# AUDIO.net
KiCad netlist of a schematic drawn in Altium Designer
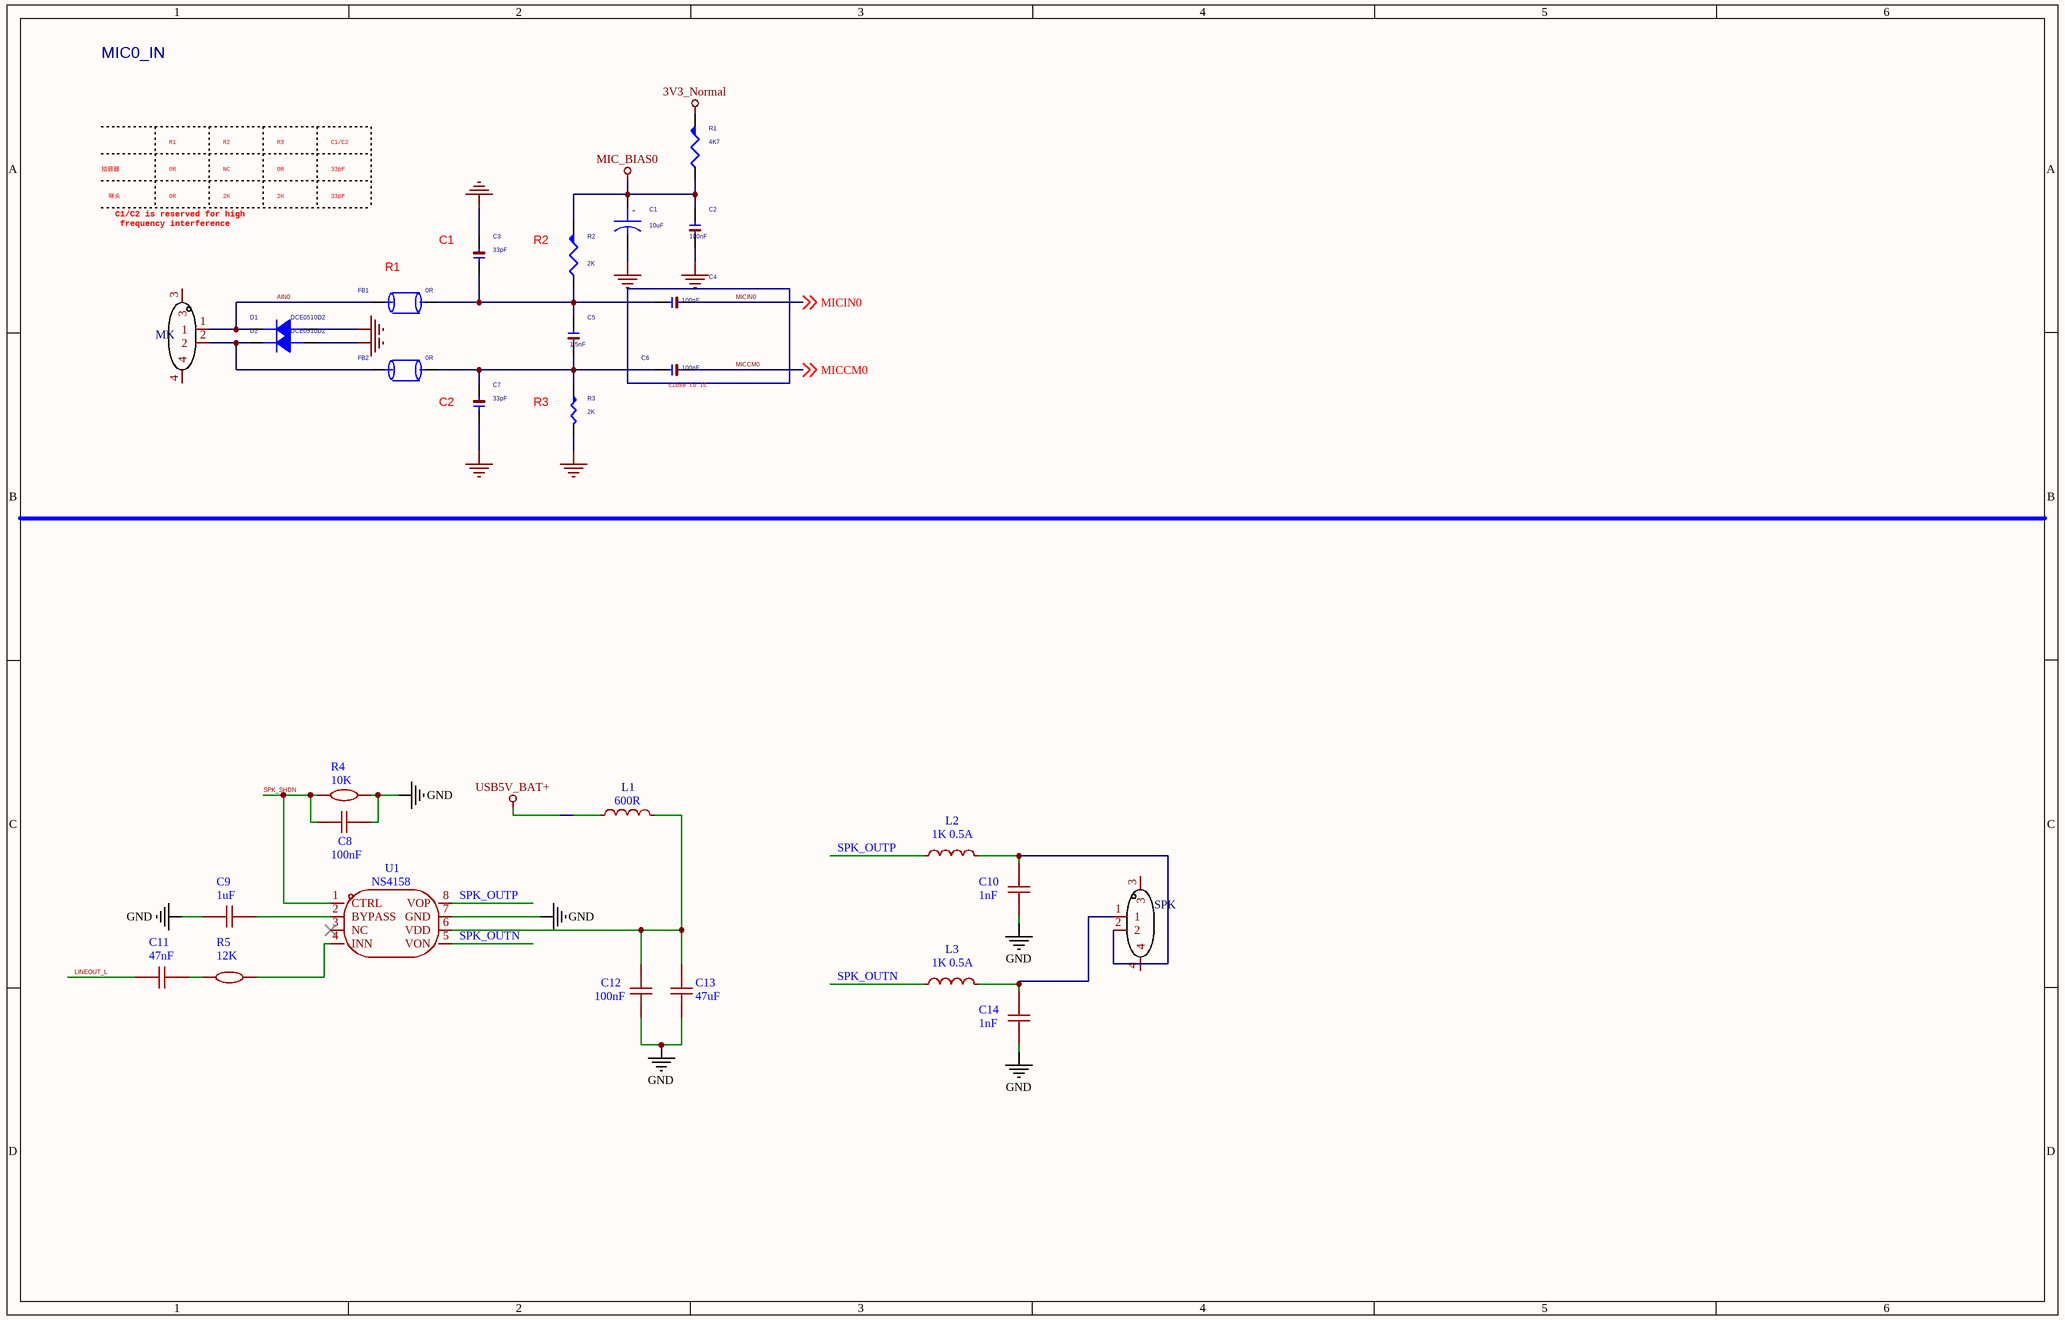
[diagram p0: AUDIO.SchDoc]

(export (version "E")
  (design (tool "Eeschema 10.0.6"))
  (components
    (comp (ref "C1") (value "10uF") (footprint "C0603") (libsource (lib "*") (part "CAP POL")))
    (comp (ref "C2") (value "100nF") (footprint "C0402") (libsource (lib "") (part "C0805_10uF_1")))
    (comp (ref "C3") (value "33pF") (footprint "C0402") (libsource (lib "*") (part "C0402")))
    (comp (ref "C4") (value "100nF") (footprint "C0402") (libsource (lib "*") (part "C0805_10uF")))
    (comp (ref "C5") (value "1.5nF") (footprint "C0402") (libsource (lib "") (part "C0805_10uF_1")))
    (comp (ref "C6") (value "100nF") (footprint "C0402") (libsource (lib "*") (part "C0805_10uF")))
    (comp (ref "C7") (value "33pF") (footprint "C0402") (libsource (lib "*") (part "C0402")))
    (comp (ref "C8")
      (value "100nF")
      (footprint "C0402")
      (libsource (lib "altium-import") (part "root_0_CAP_0805_"))
    )
    (comp (ref "C9")
      (value "1uF")
      (footprint "C0805")
      (libsource (lib "altium-import") (part "root_0_CAP_0805_"))
    )
    (comp (ref "C10")
      (value "1nF")
      (footprint "C0805")
      (libsource (lib "altium-import") (part "root_1_CAP_0805_"))
    )
    (comp (ref "C11")
      (value "47nF")
      (footprint "C0805")
      (libsource (lib "altium-import") (part "root_0_CAP_0805_"))
    )
    (comp (ref "C12")
      (value "100nF")
      (footprint "C0805")
      (libsource (lib "altium-import") (part "root_1_CAP_0805_"))
    )
    (comp (ref "C13")
      (value "47uF")
      (footprint "C1206")
      (libsource (lib "altium-import") (part "root_1_CAP_1206_"))
    )
    (comp (ref "C14")
      (value "1nF")
      (footprint "C0805")
      (libsource (lib "altium-import") (part "root_1_CAP_0805_"))
    )
    (comp (ref "CON1")
      (value "MK")
      (footprint "CONN-SMD_2P-P1.25-LT")
      (fields (field (name "MANUFACTURER PART") "HC-1.25-2PLT"))
      (libsource (lib "altium-import") (part "root_0_mirrored_HC-1.25-2PLT_"))
    )
    (comp (ref "CON2")
      (value "SPK")
      (footprint "CONN-SMD_2.0-2PLT")
      (fields (field (name "MANUFACTURER PART") "HC-1.25-2PLT"))
      (libsource (lib "altium-import") (part "root_0_HC-1.25-2PLT_"))
    )
    (comp (ref "D1")
      (value "DCE0510D2")
      (footprint "D0402_0.55x0.6")
      (libsource (lib "*") (part "DIODE_Dup1"))
    )
    (comp (ref "D2")
      (value "DCE0510D2")
      (footprint "D0402_0.55x0.6")
      (libsource (lib "*") (part "DIODE_Dup1"))
    )
    (comp (ref "FB1")
      (value "0R")
      (footprint "R0402")
      (description "BEAD/0402/120ohm/200MA")
      (fields (field (name "PART_NUMBER") "49223"))
      (libsource (lib "*") (part "BEAD"))
    )
    (comp (ref "FB2")
      (value "0R")
      (footprint "R0402")
      (description "BEAD/0402/120ohm/200MA")
      (fields (field (name "PART_NUMBER") "49223"))
      (libsource (lib "*") (part "BEAD"))
    )
    (comp (ref "L1")
      (value "600R")
      (footprint "L1206")
      (libsource (lib "altium-import") (part "root_0_CBW321609U601T_"))
    )
    (comp (ref "L2")
      (value "1K 0.5A")
      (footprint "L0805")
      (fields (field (name "MANUFACTURER PART") "SBK201209T-102Y-N"))
      (libsource (lib "altium-import") (part "root_0_SBK201209T-102Y-N_"))
    )
    (comp (ref "L3")
      (value "1K 0.5A")
      (footprint "L0805")
      (libsource (lib "altium-import") (part "root_0_SBK201209T-102Y-N_"))
    )
    (comp (ref "R1") (value "4K7") (footprint "R0402") (libsource (lib "*") (part "R-PIN-Mark")))
    (comp (ref "R2") (value "2K") (footprint "R0402") (libsource (lib "*") (part "R-PIN-Mark")))
    (comp (ref "R3") (value "2K") (footprint "R0402") (libsource (lib "*") (part "R0402")))
    (comp (ref "R4")
      (value "10K")
      (footprint "R0402")
      (libsource (lib "altium-import") (part "root_0_Res_0805_"))
    )
    (comp (ref "R5")
      (value "12K")
      (footprint "R0402")
      (libsource (lib "altium-import") (part "root_0_Res_0805_"))
    )
    (comp (ref "U1")
      (value "NS4158")
      (footprint "SOIC-8_L4.9-W3.9-P1.27-LS6.0-BL")
      (libsource (lib "altium-import") (part "root_0_NS4158_"))
    )
  )
  (nets
    (net (code "1") (name "/AIN0") (class "Default")
      (node (ref "CON1") (pin "1") (pinfunction "1_1") (pintype "passive"))
      (node (ref "D1") (pin "2") (pinfunction "K_2") (pintype "passive"))
      (node (ref "FB1") (pin "1") (pinfunction "1_1") (pintype "passive"))
    )
    (net (code "2") (name "/LINEOUT_L") (class "Default")
      (node (ref "C11") (pin "1") (pinfunction "1_1") (pintype "passive"))
    )
    (net (code "3") (name "/SPK_OUTN") (class "Default")
      (node (ref "L3") (pin "1") (pinfunction "1_1") (pintype "passive"))
      (node (ref "U1") (pin "5") (pinfunction "VON_5") (pintype "passive"))
    )
    (net (code "4") (name "/SPK_OUTP") (class "Default")
      (node (ref "L2") (pin "1") (pinfunction "1_1") (pintype "passive"))
      (node (ref "U1") (pin "8") (pinfunction "VOP_8") (pintype "passive"))
    )
    (net (code "5") (name "/SPK_SHDN") (class "Default")
      (node (ref "C8") (pin "1") (pinfunction "1_1") (pintype "passive"))
      (node (ref "R4") (pin "1") (pinfunction "1_1") (pintype "passive"))
      (node (ref "U1") (pin "1") (pinfunction "CTRL_1") (pintype "passive"))
    )
    (net (code "6") (name "3V3_Normal") (class "Default")
      (node (ref "R1") (pin "1") (pinfunction "1_1") (pintype "passive"))
    )
    (net (code "7") (name "GND") (class "Default")
      (node (ref "C1") (pin "2") (pinfunction "2_2") (pintype "passive"))
      (node (ref "C10") (pin "1") (pinfunction "1_1") (pintype "passive"))
      (node (ref "C12") (pin "1") (pinfunction "1_1") (pintype "passive"))
      (node (ref "C13") (pin "1") (pinfunction "1_1") (pintype "passive"))
      (node (ref "C14") (pin "1") (pinfunction "1_1") (pintype "passive"))
      (node (ref "C2") (pin "2") (pinfunction "2_2") (pintype "passive"))
      (node (ref "C3") (pin "1") (pinfunction "1_1") (pintype "passive"))
      (node (ref "C7") (pin "2") (pinfunction "2_2") (pintype "passive"))
      (node (ref "C8") (pin "2") (pinfunction "2_2") (pintype "passive"))
      (node (ref "C9") (pin "1") (pinfunction "1_1") (pintype "passive"))
      (node (ref "D1") (pin "1") (pinfunction "A_1") (pintype "passive"))
      (node (ref "D2") (pin "1") (pinfunction "A_1") (pintype "passive"))
      (node (ref "R3") (pin "2") (pinfunction "2_2") (pintype "passive"))
      (node (ref "R4") (pin "2") (pinfunction "2_2") (pintype "passive"))
      (node (ref "U1") (pin "7") (pinfunction "GND_7") (pintype "passive"))
    )
    (net (code "8") (name "MICCM0") (class "Default")
      (node (ref "C6") (pin "2") (pinfunction "2_2") (pintype "passive"))
    )
    (net (code "9") (name "MICIN0") (class "Default")
      (node (ref "C4") (pin "2") (pinfunction "2_2") (pintype "passive"))
    )
    (net (code "10") (name "MIC_BIAS0") (class "Default")
      (node (ref "C1") (pin "1") (pinfunction "1_1") (pintype "passive"))
      (node (ref "C2") (pin "1") (pinfunction "1_1") (pintype "passive"))
      (node (ref "R1") (pin "2") (pinfunction "2_2") (pintype "passive"))
      (node (ref "R2") (pin "1") (pinfunction "1_1") (pintype "passive"))
    )
    (net (code "11") (name "Net-(C3-Pad2)") (class "Default")
      (node (ref "C3") (pin "2") (pinfunction "2_2") (pintype "passive"))
      (node (ref "C4") (pin "1") (pinfunction "1_1") (pintype "passive"))
      (node (ref "C5") (pin "1") (pinfunction "1_1") (pintype "passive"))
      (node (ref "FB1") (pin "2") (pinfunction "2_2") (pintype "passive"))
      (node (ref "R2") (pin "2") (pinfunction "2_2") (pintype "passive"))
    )
    (net (code "12") (name "Net-(C5-Pad2)") (class "Default")
      (node (ref "C5") (pin "2") (pinfunction "2_2") (pintype "passive"))
      (node (ref "C6") (pin "1") (pinfunction "1_1") (pintype "passive"))
      (node (ref "C7") (pin "1") (pinfunction "1_1") (pintype "passive"))
      (node (ref "FB2") (pin "2") (pinfunction "2_2") (pintype "passive"))
      (node (ref "R3") (pin "1") (pinfunction "1_1") (pintype "passive"))
    )
    (net (code "13") (name "Net-(C10-Pad2)") (class "Default")
      (node (ref "C10") (pin "2") (pinfunction "2_2") (pintype "passive"))
      (node (ref "CON2") (pin "2") (pinfunction "2_2") (pintype "passive"))
      (node (ref "L2") (pin "2") (pinfunction "2_2") (pintype "passive"))
    )
    (net (code "14") (name "Net-(C11-Pad2)") (class "Default")
      (node (ref "C11") (pin "2") (pinfunction "2_2") (pintype "passive"))
      (node (ref "R5") (pin "1") (pinfunction "1_1") (pintype "passive"))
    )
    (net (code "15") (name "Net-(C14-Pad2)") (class "Default")
      (node (ref "C14") (pin "2") (pinfunction "2_2") (pintype "passive"))
      (node (ref "CON2") (pin "1") (pinfunction "1_1") (pintype "passive"))
      (node (ref "L3") (pin "2") (pinfunction "2_2") (pintype "passive"))
    )
    (net (code "16") (name "Net-(D2-K)") (class "Default")
      (node (ref "CON1") (pin "2") (pinfunction "2_2") (pintype "passive"))
      (node (ref "D2") (pin "2") (pinfunction "K_2") (pintype "passive"))
      (node (ref "FB2") (pin "1") (pinfunction "1_1") (pintype "passive"))
    )
    (net (code "17") (name "Net-(U1-BYPASS)") (class "Default")
      (node (ref "C9") (pin "2") (pinfunction "2_2") (pintype "passive"))
      (node (ref "U1") (pin "2") (pinfunction "BYPASS_2") (pintype "passive"))
    )
    (net (code "18") (name "Net-(U1-INN)") (class "Default")
      (node (ref "R5") (pin "2") (pinfunction "2_2") (pintype "passive"))
      (node (ref "U1") (pin "4") (pinfunction "INN_4") (pintype "passive"))
    )
    (net (code "19") (name "Net-(U1-VDD)") (class "Default")
      (node (ref "C12") (pin "2") (pinfunction "2_2") (pintype "passive"))
      (node (ref "C13") (pin "2") (pinfunction "2_2") (pintype "passive"))
      (node (ref "L1") (pin "2") (pinfunction "2_2") (pintype "passive"))
      (node (ref "U1") (pin "6") (pinfunction "VDD_6") (pintype "passive"))
    )
    (net (code "20") (name "USB5V_BAT+") (class "Default")
      (node (ref "L1") (pin "1") (pinfunction "1_1") (pintype "passive"))
    )
    (net (code "21") (name "unconnected-(CON1-Pad3)") (class "Default")
      (node (ref "CON1") (pin "3") (pinfunction "3_3") (pintype "passive"))
    )
    (net (code "22") (name "unconnected-(CON1-Pad4)") (class "Default")
      (node (ref "CON1") (pin "4") (pinfunction "4_4") (pintype "passive"))
    )
    (net (code "23") (name "unconnected-(CON2-Pad3)") (class "Default")
      (node (ref "CON2") (pin "3") (pinfunction "3_3") (pintype "passive"))
    )
    (net (code "24") (name "unconnected-(CON2-Pad4)") (class "Default")
      (node (ref "CON2") (pin "4") (pinfunction "4_4") (pintype "passive"))
    )
    (net (code "25") (name "unconnected-(U1-NC-Pad3)") (class "Default")
      (node (ref "U1") (pin "3") (pinfunction "NC_3") (pintype "passive+no_connect"))
    )
  )
)
